# 780-00055_rev1_Pg2_SCH_NRES_Temp_Meas_8-.net
KiCad netlist of a schematic drawn in Altium Designer
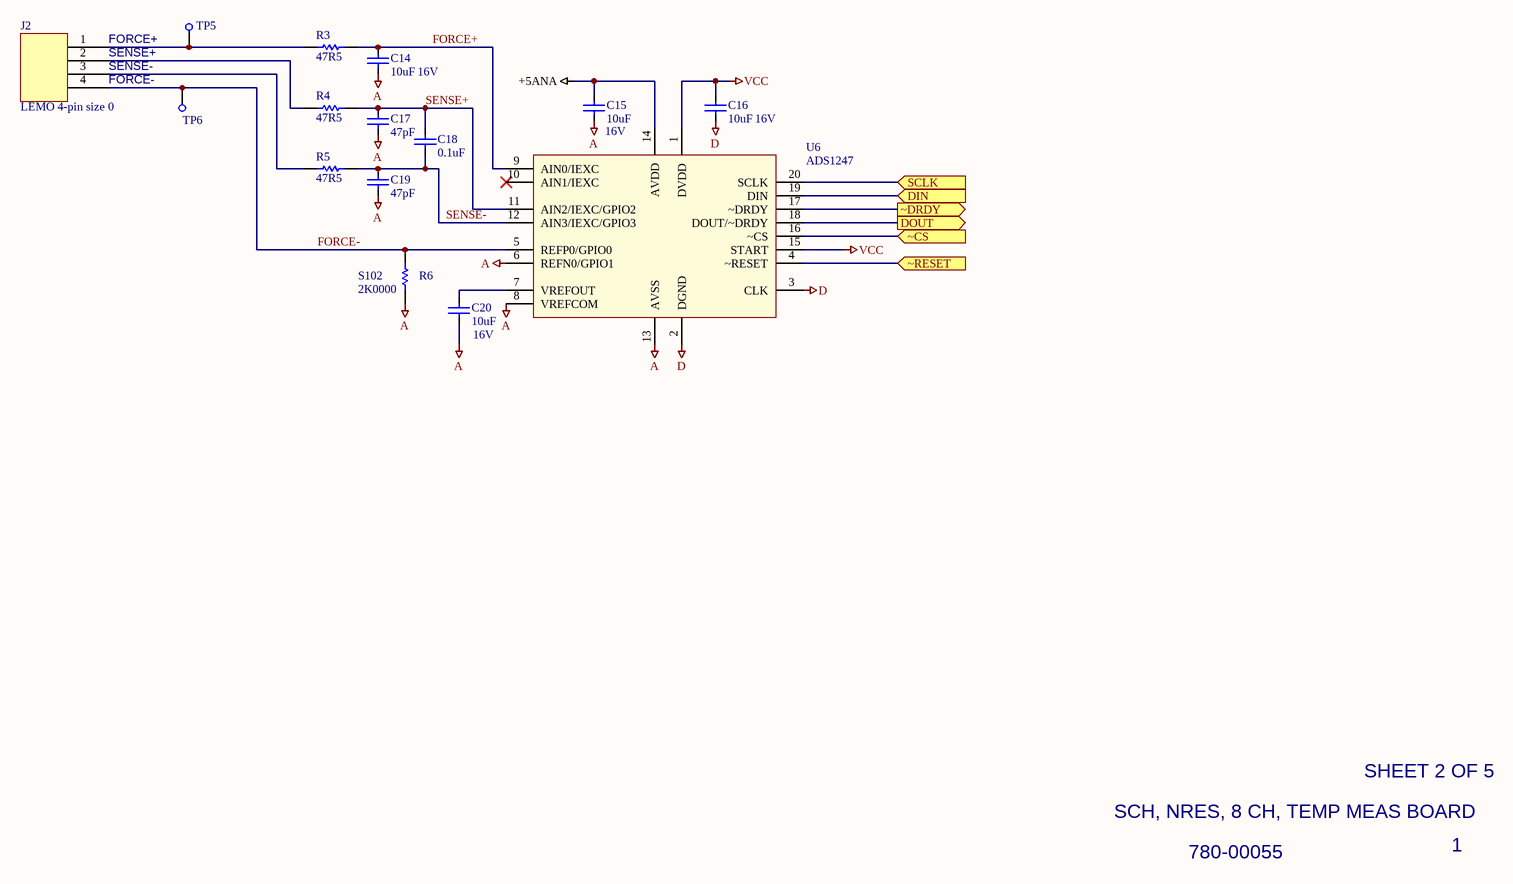
[diagram p0: 780-00055, rev1, Pg2, SCH, NRES Temp Meas, 8-Chan RTD .SchDoc]

(export (version "E")
  (design (tool "Eeschema 10.0.6"))
  (components
    (comp (ref "C14")
      (value "16V")
      (footprint "SMD_0805")
      (description "Capacitor")
      (fields (field (name "ALTIUM_VALUE") "10uF"))
      (libsource (lib "Richs Schematic Components") (part "Cap SMD"))
    )
    (comp (ref "C15")
      (value "16V")
      (footprint "SMD_0805")
      (description "Capacitor")
      (fields (field (name "ALTIUM_VALUE") "10uF"))
      (libsource (lib "Richs Schematic Components") (part "Cap SMD"))
    )
    (comp (ref "C16")
      (value "16V")
      (footprint "SMD_0805")
      (description "Capacitor")
      (fields (field (name "ALTIUM_VALUE") "10uF"))
      (libsource (lib "Richs Schematic Components") (part "Cap SMD"))
    )
    (comp (ref "C17")
      (value "47pF")
      (footprint "SMD_0805")
      (description "Capacitor")
      (fields (field (name "Comment") "Cap SMD"))
      (libsource (lib "Richs Schematic Components") (part "Cap SMD"))
    )
    (comp (ref "C18")
      (value "0.1uF")
      (footprint "SMD_0805")
      (description "Capacitor")
      (fields (field (name "Comment") "Cap SMD"))
      (libsource (lib "Richs Schematic Components") (part "Cap SMD"))
    )
    (comp (ref "C19")
      (value "47pF")
      (footprint "SMD_0805")
      (description "Capacitor")
      (fields (field (name "Comment") "Cap SMD"))
      (libsource (lib "Richs Schematic Components") (part "Cap SMD"))
    )
    (comp (ref "C20")
      (value "16V")
      (footprint "SMD_0805")
      (description "Capacitor")
      (fields (field (name "ALTIUM_VALUE") "10uF"))
      (libsource (lib "Richs Schematic Components") (part "Cap SMD"))
    )
    (comp (ref "J2")
      (value "LEMO 4-pin size 0")
      (footprint "LEMO Size 0, 4-pin PCB")
      (libsource (lib "Richs Schematic Components") (part "LEMO Size 0, 4 pin, PCB"))
    )
    (comp (ref "R3")
      (value "47R5")
      (footprint "SMD_0805")
      (description "Resistor 0805")
      (fields (field (name "MANUFACTURER") "Vishay/Dale") (field (name "Comment") "Res 0805"))
      (libsource (lib "Richs Schematic Components") (part "Res SMD"))
    )
    (comp (ref "R4")
      (value "47R5")
      (footprint "SMD_0805")
      (description "Resistor 0805")
      (fields (field (name "MANUFACTURER") "Vishay/Dale") (field (name "Comment") "Res 0805"))
      (libsource (lib "Richs Schematic Components") (part "Res SMD"))
    )
    (comp (ref "R5")
      (value "47R5")
      (footprint "SMD_0805")
      (description "Resistor 0805")
      (fields (field (name "MANUFACTURER") "Vishay/Dale") (field (name "Comment") "Res 0805"))
      (libsource (lib "Richs Schematic Components") (part "Res SMD"))
    )
    (comp (ref "R6")
      (value "S102")
      (footprint "Vishay S102 series")
      (description "Vishay Foil Resistor")
      (fields (field (name "ALTIUM_VALUE") "2K0000"))
      (libsource (lib "Richs Schematic Components") (part "RES TH Radial"))
    )
    (comp (ref "TP5")
      (value "Test point")
      (footprint "Protel 99SE BANKS PCB:PAD_80D_052H")
      (description "Test Point")
      (fields (field (name "MANUFACTURER") "Keystone"))
      (libsource (lib "Richs Schematic Components") (part "Test point"))
    )
    (comp (ref "TP6")
      (value "Test point")
      (footprint "Protel 99SE BANKS PCB:PAD_80D_052H")
      (description "Test Point")
      (fields (field (name "MANUFACTURER") "Keystone"))
      (libsource (lib "Richs Schematic Components") (part "Test point"))
    )
    (comp (ref "U6")
      (value "ADS1247")
      (footprint "TSSOP20")
      (description "24bit ADC for Temp Sensors")
      (fields (field (name "MANUFACTURER") "TI"))
      (libsource (lib "Richs Schematic Components") (part "ADS1247"))
    )
  )
  (nets
    (net (code "1") (name "+5ANA") (class "Default")
      (node (ref "C15") (pin "2") (pinfunction "2_2") (pintype "passive"))
      (node (ref "U6") (pin "14") (pinfunction "AVDD_14") (pintype "passive"))
    )
    (net (code "2") (name "/DIN") (class "Default")
      (node (ref "U6") (pin "19") (pinfunction "DIN_19") (pintype "passive"))
    )
    (net (code "3") (name "/DOUT") (class "Default")
      (node (ref "U6") (pin "18") (pinfunction "DOUT/~DRDY_18") (pintype "passive"))
    )
    (net (code "4") (name "/FORCE+") (class "Default")
      (node (ref "C14") (pin "2") (pinfunction "2_2") (pintype "passive"))
      (node (ref "R3") (pin "2") (pinfunction "2_2") (pintype "passive"))
      (node (ref "U6") (pin "9") (pinfunction "AIN0/IEXC_9") (pintype "passive"))
    )
    (net (code "5") (name "/FORCE-") (class "Default")
      (node (ref "J2") (pin "4") (pinfunction "S32_4") (pintype "passive"))
      (node (ref "R6") (pin "2") (pinfunction "2_2") (pintype "passive"))
      (node (ref "TP6") (pin "1") (pinfunction "TP_1") (pintype "passive"))
      (node (ref "U6") (pin "5") (pinfunction "REFP0/GPIO0_5") (pintype "passive"))
    )
    (net (code "6") (name "/SCLK") (class "Default")
      (node (ref "U6") (pin "20") (pinfunction "SCLK_20") (pintype "passive"))
    )
    (net (code "7") (name "/SENSE+") (class "Default")
      (node (ref "C17") (pin "2") (pinfunction "2_2") (pintype "passive"))
      (node (ref "C18") (pin "2") (pinfunction "2_2") (pintype "passive"))
      (node (ref "R4") (pin "2") (pinfunction "2_2") (pintype "passive"))
      (node (ref "U6") (pin "11") (pinfunction "AIN2/IEXC/GPIO2_11") (pintype "passive"))
    )
    (net (code "8") (name "/SENSE-") (class "Default")
      (node (ref "C18") (pin "1") (pinfunction "1_1") (pintype "passive"))
      (node (ref "C19") (pin "2") (pinfunction "2_2") (pintype "passive"))
      (node (ref "R5") (pin "2") (pinfunction "2_2") (pintype "passive"))
      (node (ref "U6") (pin "12") (pinfunction "AIN3/IEXC/GPIO3_12") (pintype "passive"))
    )
    (net (code "9") (name "/~CS") (class "Default")
      (node (ref "U6") (pin "16") (pinfunction "~CS_16") (pintype "passive"))
    )
    (net (code "10") (name "/~DRDY") (class "Default")
      (node (ref "U6") (pin "17") (pinfunction "~DRDY_17") (pintype "passive"))
    )
    (net (code "11") (name "/~RESET") (class "Default")
      (node (ref "U6") (pin "4") (pinfunction "~RESET_4") (pintype "passive"))
    )
    (net (code "12") (name "A") (class "Default")
      (node (ref "C14") (pin "1") (pinfunction "1_1") (pintype "passive"))
      (node (ref "C15") (pin "1") (pinfunction "1_1") (pintype "passive"))
      (node (ref "C17") (pin "1") (pinfunction "1_1") (pintype "passive"))
      (node (ref "C19") (pin "1") (pinfunction "1_1") (pintype "passive"))
      (node (ref "C20") (pin "1") (pinfunction "1_1") (pintype "passive"))
      (node (ref "R6") (pin "1") (pinfunction "1_1") (pintype "passive"))
      (node (ref "U6") (pin "13") (pinfunction "AVSS_13") (pintype "passive"))
      (node (ref "U6") (pin "6") (pinfunction "REFN0/GPIO1_6") (pintype "passive"))
      (node (ref "U6") (pin "8") (pinfunction "VREFCOM_8") (pintype "passive"))
    )
    (net (code "13") (name "D") (class "Default")
      (node (ref "C16") (pin "1") (pinfunction "1_1") (pintype "passive"))
      (node (ref "U6") (pin "2") (pinfunction "DGND_2") (pintype "passive"))
      (node (ref "U6") (pin "3") (pinfunction "CLK_3") (pintype "passive"))
    )
    (net (code "14") (name "Net-(J2-S29)") (class "Default")
      (node (ref "J2") (pin "1") (pinfunction "S29_1") (pintype "passive"))
      (node (ref "R3") (pin "1") (pinfunction "1_1") (pintype "passive"))
      (node (ref "TP5") (pin "1") (pinfunction "TP_1") (pintype "passive"))
    )
    (net (code "15") (name "Net-(J2-S30)") (class "Default")
      (node (ref "J2") (pin "2") (pinfunction "S30_2") (pintype "passive"))
      (node (ref "R4") (pin "1") (pinfunction "1_1") (pintype "passive"))
    )
    (net (code "16") (name "Net-(J2-S31)") (class "Default")
      (node (ref "J2") (pin "3") (pinfunction "S31_3") (pintype "passive"))
      (node (ref "R5") (pin "1") (pinfunction "1_1") (pintype "passive"))
    )
    (net (code "17") (name "Net-(U6-VREFOUT)") (class "Default")
      (node (ref "C20") (pin "2") (pinfunction "2_2") (pintype "passive"))
      (node (ref "U6") (pin "7") (pinfunction "VREFOUT_7") (pintype "passive"))
    )
    (net (code "18") (name "VCC") (class "Default")
      (node (ref "C16") (pin "2") (pinfunction "2_2") (pintype "passive"))
      (node (ref "U6") (pin "1") (pinfunction "DVDD_1") (pintype "passive"))
      (node (ref "U6") (pin "15") (pinfunction "START_15") (pintype "passive"))
    )
    (net (code "19") (name "unconnected-(U6-AIN1{slash}IEXC-Pad10)") (class "Default")
      (node (ref "U6") (pin "10") (pinfunction "AIN1/IEXC_10") (pintype "passive+no_connect"))
    )
  )
)
